# loop-rs232.net
KiCad netlist of a schematic drawn in EAGLE
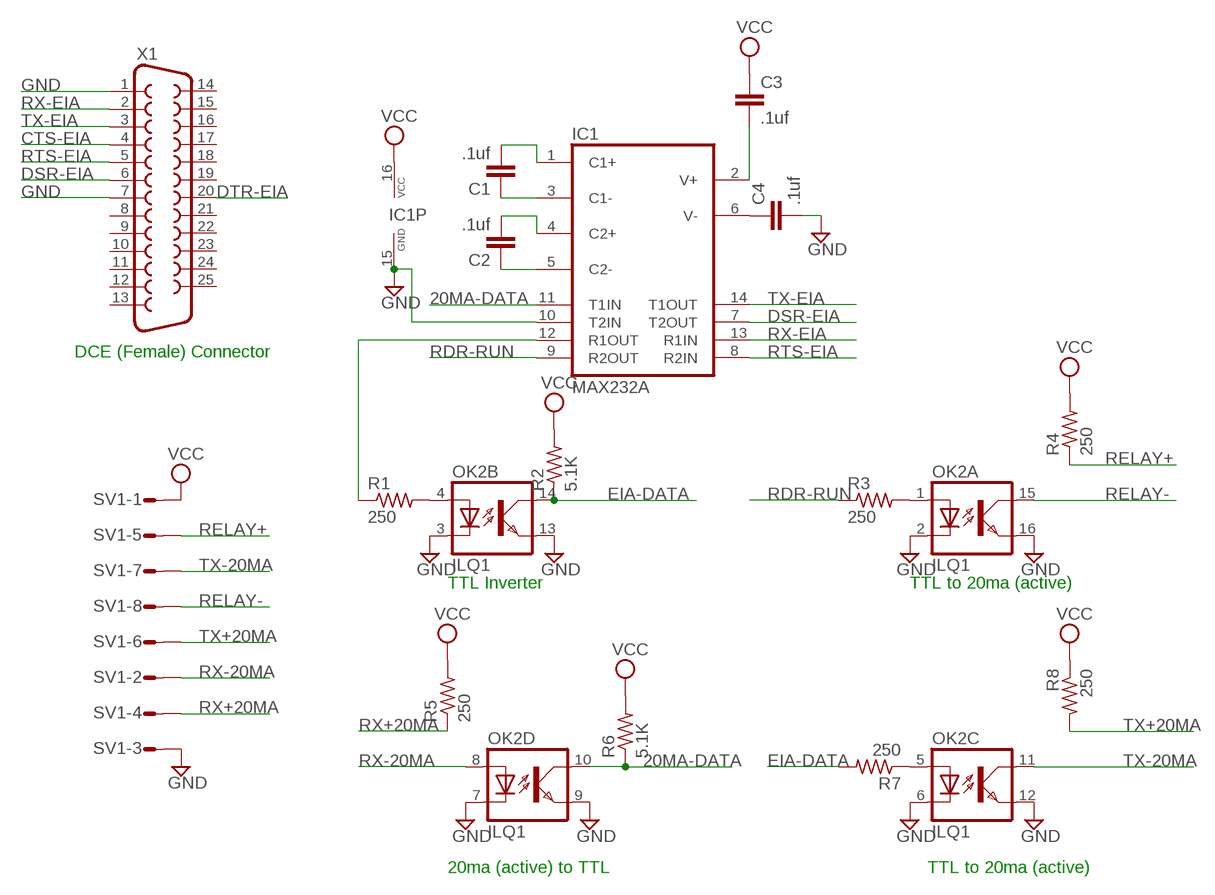
[diagram p0: schematic, sheet 1]

(export (version "E")
  (design (tool "Eeschema 10.0.6"))
  (components
    (comp (ref "C1")
      (value ".1uf")
      (footprint "eagle-import:C050-025X075")
      (libsource (lib "eagle-import") (part "C-EU050-025X075"))
    )
    (comp (ref "C2")
      (value ".1uf")
      (footprint "eagle-import:C050-025X075")
      (libsource (lib "eagle-import") (part "C-EU050-025X075"))
    )
    (comp (ref "C3")
      (value ".1uf")
      (footprint "eagle-import:C050-025X075")
      (libsource (lib "eagle-import") (part "C-EU050-025X075"))
    )
    (comp (ref "C4")
      (value ".1uf")
      (footprint "eagle-import:C050-025X075")
      (libsource (lib "eagle-import") (part "C-EU050-025X075"))
    )
    (comp (ref "IC1")
      (value "MAX232A")
      (footprint "eagle-import:DIL16")
      (fields (field (name "MF") "MAXIM") (field (name "MPN") "MAX232ACPE+"))
      (libsource (lib "eagle-import") (part "MAX232"))
    )
    (comp (ref "OK2")
      (value "ILQ1")
      (footprint "eagle-import:DIL16")
      (fields (field (name "MF") "VISHAY/TELEFUNKEN"))
      (libsource (lib "eagle-import") (part "ILQ1"))
    )
    (comp (ref "R1")
      (value "250")
      (footprint "eagle-import:0207_10")
      (libsource (lib "eagle-import") (part "R-US_0207/10"))
    )
    (comp (ref "R2")
      (value "5.1K")
      (footprint "eagle-import:0207_10")
      (libsource (lib "eagle-import") (part "R-US_0207/10"))
    )
    (comp (ref "R3")
      (value "250")
      (footprint "eagle-import:0207_10")
      (libsource (lib "eagle-import") (part "R-US_0207/10"))
    )
    (comp (ref "R4")
      (value "250")
      (footprint "eagle-import:0207_10")
      (libsource (lib "eagle-import") (part "R-US_0207/10"))
    )
    (comp (ref "R5")
      (value "250")
      (footprint "eagle-import:0207_10")
      (libsource (lib "eagle-import") (part "R-US_0207/10"))
    )
    (comp (ref "R6")
      (value "5.1K")
      (footprint "eagle-import:0207_10")
      (libsource (lib "eagle-import") (part "R-US_0207/10"))
    )
    (comp (ref "R7")
      (value "250")
      (footprint "eagle-import:0207_10")
      (libsource (lib "eagle-import") (part "R-US_0207/10"))
    )
    (comp (ref "R8")
      (value "250")
      (footprint "eagle-import:0207_10")
      (libsource (lib "eagle-import") (part "R-US_0207/10"))
    )
    (comp (ref "SV1")
      (value "S08P")
      (footprint "eagle-import:S08P")
      (libsource (lib "eagle-import") (part "S08P"))
    )
    (comp (ref "X1")
      (value "F25H")
      (footprint "eagle-import:F25H")
      (libsource (lib "eagle-import") (part "F25H"))
    )
  )
  (nets
    (net (code "1") (name "/20MA-DATA") (class "Default")
      (node (ref "IC1") (pin "11") (pinfunction "T1IN_11") (pintype "input"))
      (node (ref "OK2") (pin "10") (pinfunction "COL_10") (pintype "passive"))
      (node (ref "R6") (pin "1") (pinfunction "1_1") (pintype "passive"))
    )
    (net (code "2") (name "/CTS-EIA") (class "Default")
      (node (ref "X1") (pin "4") (pinfunction "4_4") (pintype "passive"))
    )
    (net (code "3") (name "/DSR-EIA") (class "Default")
      (node (ref "IC1") (pin "7") (pinfunction "T2OUT_7") (pintype "output"))
      (node (ref "X1") (pin "6") (pinfunction "6_6") (pintype "passive"))
    )
    (net (code "4") (name "/DTR-EIA") (class "Default")
      (node (ref "X1") (pin "20") (pinfunction "20_20") (pintype "passive"))
    )
    (net (code "5") (name "/EIA-DATA") (class "Default")
      (node (ref "OK2") (pin "14") (pinfunction "COL_14") (pintype "passive"))
      (node (ref "R2") (pin "1") (pinfunction "1_1") (pintype "passive"))
      (node (ref "R7") (pin "2") (pinfunction "2_2") (pintype "passive"))
    )
    (net (code "6") (name "/RDR-RUN") (class "Default")
      (node (ref "IC1") (pin "9") (pinfunction "R2OUT_9") (pintype "output"))
      (node (ref "R3") (pin "1") (pinfunction "1_1") (pintype "passive"))
    )
    (net (code "7") (name "/RELAY+") (class "Default")
      (node (ref "R4") (pin "1") (pinfunction "1_1") (pintype "passive"))
      (node (ref "SV1") (pin "5") (pinfunction "S_5") (pintype "passive"))
    )
    (net (code "8") (name "/RELAY-") (class "Default")
      (node (ref "OK2") (pin "15") (pinfunction "COL_15") (pintype "passive"))
      (node (ref "SV1") (pin "8") (pinfunction "S_8") (pintype "passive"))
    )
    (net (code "9") (name "/RTS-EIA") (class "Default")
      (node (ref "IC1") (pin "8") (pinfunction "R2IN_8") (pintype "input"))
      (node (ref "X1") (pin "5") (pinfunction "5_5") (pintype "passive"))
    )
    (net (code "10") (name "/RX+20MA") (class "Default")
      (node (ref "R5") (pin "1") (pinfunction "1_1") (pintype "passive"))
      (node (ref "SV1") (pin "4") (pinfunction "S_4") (pintype "passive"))
    )
    (net (code "11") (name "/RX-20MA") (class "Default")
      (node (ref "OK2") (pin "8") (pinfunction "A_8") (pintype "passive"))
      (node (ref "SV1") (pin "2") (pinfunction "S_2") (pintype "passive"))
    )
    (net (code "12") (name "/RX-EIA") (class "Default")
      (node (ref "IC1") (pin "13") (pinfunction "R1IN_13") (pintype "input"))
      (node (ref "X1") (pin "2") (pinfunction "2_2") (pintype "passive"))
    )
    (net (code "13") (name "/TX+20MA") (class "Default")
      (node (ref "R8") (pin "2") (pinfunction "2_2") (pintype "passive"))
      (node (ref "SV1") (pin "6") (pinfunction "S_6") (pintype "passive"))
    )
    (net (code "14") (name "/TX-20MA") (class "Default")
      (node (ref "OK2") (pin "11") (pinfunction "COL_11") (pintype "passive"))
      (node (ref "SV1") (pin "7") (pinfunction "S_7") (pintype "passive"))
    )
    (net (code "15") (name "/TX-EIA") (class "Default")
      (node (ref "IC1") (pin "14") (pinfunction "T1OUT_14") (pintype "output"))
      (node (ref "X1") (pin "3") (pinfunction "3_3") (pintype "passive"))
    )
    (net (code "16") (name "GND") (class "Default")
      (node (ref "C4") (pin "2") (pinfunction "2_2") (pintype "passive"))
      (node (ref "IC1") (pin "10") (pinfunction "T2IN_10") (pintype "input"))
      (node (ref "IC1") (pin "15") (pinfunction "GND_15") (pintype "power_in"))
      (node (ref "OK2") (pin "12") (pinfunction "EMIT_12") (pintype "passive"))
      (node (ref "OK2") (pin "13") (pinfunction "EMIT_13") (pintype "passive"))
      (node (ref "OK2") (pin "16") (pinfunction "EMIT_16") (pintype "passive"))
      (node (ref "OK2") (pin "2") (pinfunction "C_2") (pintype "passive"))
      (node (ref "OK2") (pin "3") (pinfunction "C_3") (pintype "passive"))
      (node (ref "OK2") (pin "6") (pinfunction "C_6") (pintype "passive"))
      (node (ref "OK2") (pin "7") (pinfunction "C_7") (pintype "passive"))
      (node (ref "OK2") (pin "9") (pinfunction "EMIT_9") (pintype "passive"))
      (node (ref "SV1") (pin "3") (pinfunction "S_3") (pintype "passive"))
      (node (ref "X1") (pin "1") (pinfunction "1_1") (pintype "passive"))
      (node (ref "X1") (pin "7") (pinfunction "7_7") (pintype "passive"))
    )
    (net (code "17") (name "Net-(IC1A-C1+)") (class "Default")
      (node (ref "C1") (pin "2") (pinfunction "2_2") (pintype "passive"))
      (node (ref "IC1") (pin "1") (pinfunction "C1+_1") (pintype "bidirectional"))
    )
    (net (code "18") (name "Net-(IC1A-C1-)") (class "Default")
      (node (ref "C1") (pin "1") (pinfunction "1_1") (pintype "passive"))
      (node (ref "IC1") (pin "3") (pinfunction "C1-_3") (pintype "bidirectional"))
    )
    (net (code "19") (name "Net-(IC1A-C2+)") (class "Default")
      (node (ref "C2") (pin "2") (pinfunction "2_2") (pintype "passive"))
      (node (ref "IC1") (pin "4") (pinfunction "C2+_4") (pintype "bidirectional"))
    )
    (net (code "20") (name "Net-(IC1A-C2-)") (class "Default")
      (node (ref "C2") (pin "1") (pinfunction "1_1") (pintype "passive"))
      (node (ref "IC1") (pin "5") (pinfunction "C2-_5") (pintype "bidirectional"))
    )
    (net (code "21") (name "Net-(IC1A-R1OUT)") (class "Default")
      (node (ref "IC1") (pin "12") (pinfunction "R1OUT_12") (pintype "output"))
      (node (ref "R1") (pin "1") (pinfunction "1_1") (pintype "passive"))
    )
    (net (code "22") (name "Net-(IC1A-V+)") (class "Default")
      (node (ref "C3") (pin "2") (pinfunction "2_2") (pintype "passive"))
      (node (ref "IC1") (pin "2") (pinfunction "V+_2") (pintype "bidirectional"))
    )
    (net (code "23") (name "Net-(IC1A-V-)") (class "Default")
      (node (ref "C4") (pin "1") (pinfunction "1_1") (pintype "passive"))
      (node (ref "IC1") (pin "6") (pinfunction "V-_6") (pintype "bidirectional"))
    )
    (net (code "24") (name "Net-(OK2A-A)") (class "Default")
      (node (ref "OK2") (pin "1") (pinfunction "A_1") (pintype "passive"))
      (node (ref "R3") (pin "2") (pinfunction "2_2") (pintype "passive"))
    )
    (net (code "25") (name "Net-(OK2B-A)") (class "Default")
      (node (ref "OK2") (pin "4") (pinfunction "A_4") (pintype "passive"))
      (node (ref "R1") (pin "2") (pinfunction "2_2") (pintype "passive"))
    )
    (net (code "26") (name "Net-(OK2C-A)") (class "Default")
      (node (ref "OK2") (pin "5") (pinfunction "A_5") (pintype "passive"))
      (node (ref "R7") (pin "1") (pinfunction "1_1") (pintype "passive"))
    )
    (net (code "27") (name "VCC") (class "Default")
      (node (ref "C3") (pin "1") (pinfunction "1_1") (pintype "passive"))
      (node (ref "IC1") (pin "16") (pinfunction "VCC_16") (pintype "power_in"))
      (node (ref "R2") (pin "2") (pinfunction "2_2") (pintype "passive"))
      (node (ref "R4") (pin "2") (pinfunction "2_2") (pintype "passive"))
      (node (ref "R5") (pin "2") (pinfunction "2_2") (pintype "passive"))
      (node (ref "R6") (pin "2") (pinfunction "2_2") (pintype "passive"))
      (node (ref "R8") (pin "1") (pinfunction "1_1") (pintype "passive"))
      (node (ref "SV1") (pin "1") (pinfunction "S_1") (pintype "passive"))
    )
    (net (code "28") (name "unconnected-(X1-Pad8)") (class "Default")
      (node (ref "X1") (pin "8") (pinfunction "8_8") (pintype "passive"))
    )
    (net (code "29") (name "unconnected-(X1-Pad9)") (class "Default")
      (node (ref "X1") (pin "9") (pinfunction "9_9") (pintype "passive"))
    )
    (net (code "30") (name "unconnected-(X1-Pad10)") (class "Default")
      (node (ref "X1") (pin "10") (pinfunction "10_10") (pintype "passive"))
    )
    (net (code "31") (name "unconnected-(X1-Pad11)") (class "Default")
      (node (ref "X1") (pin "11") (pinfunction "11_11") (pintype "passive"))
    )
    (net (code "32") (name "unconnected-(X1-Pad12)") (class "Default")
      (node (ref "X1") (pin "12") (pinfunction "12_12") (pintype "passive"))
    )
    (net (code "33") (name "unconnected-(X1-Pad13)") (class "Default")
      (node (ref "X1") (pin "13") (pinfunction "13_13") (pintype "passive"))
    )
    (net (code "34") (name "unconnected-(X1-Pad14)") (class "Default")
      (node (ref "X1") (pin "14") (pinfunction "14_14") (pintype "passive"))
    )
    (net (code "35") (name "unconnected-(X1-Pad15)") (class "Default")
      (node (ref "X1") (pin "15") (pinfunction "15_15") (pintype "passive"))
    )
    (net (code "36") (name "unconnected-(X1-Pad16)") (class "Default")
      (node (ref "X1") (pin "16") (pinfunction "16_16") (pintype "passive"))
    )
    (net (code "37") (name "unconnected-(X1-Pad17)") (class "Default")
      (node (ref "X1") (pin "17") (pinfunction "17_17") (pintype "passive"))
    )
    (net (code "38") (name "unconnected-(X1-Pad18)") (class "Default")
      (node (ref "X1") (pin "18") (pinfunction "18_18") (pintype "passive"))
    )
    (net (code "39") (name "unconnected-(X1-Pad19)") (class "Default")
      (node (ref "X1") (pin "19") (pinfunction "19_19") (pintype "passive"))
    )
    (net (code "40") (name "unconnected-(X1-Pad21)") (class "Default")
      (node (ref "X1") (pin "21") (pinfunction "21_21") (pintype "passive"))
    )
    (net (code "41") (name "unconnected-(X1-Pad22)") (class "Default")
      (node (ref "X1") (pin "22") (pinfunction "22_22") (pintype "passive"))
    )
    (net (code "42") (name "unconnected-(X1-Pad23)") (class "Default")
      (node (ref "X1") (pin "23") (pinfunction "23_23") (pintype "passive"))
    )
    (net (code "43") (name "unconnected-(X1-Pad24)") (class "Default")
      (node (ref "X1") (pin "24") (pinfunction "24_24") (pintype "passive"))
    )
    (net (code "44") (name "unconnected-(X1-Pad25)") (class "Default")
      (node (ref "X1") (pin "25") (pinfunction "25_25") (pintype "passive"))
    )
  )
)
